# DESIGN7RA.net
KiCad netlist of a schematic drawn in EAGLE
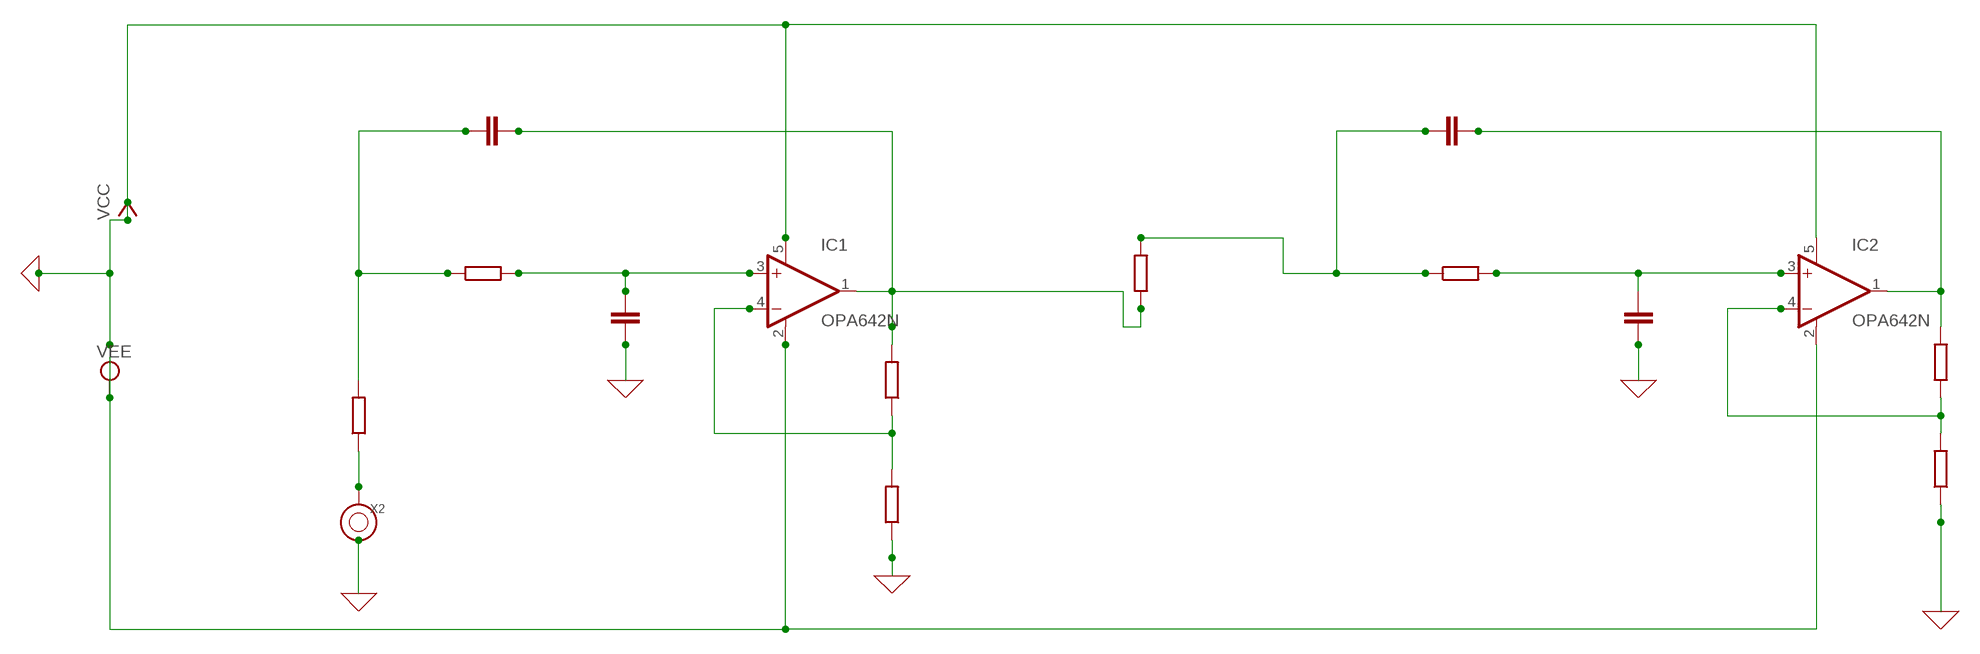
[diagram p0: schematic, sheet 1]

(export (version "E")
  (design (tool "Eeschema 10.0.6"))
  (components
    (comp (ref "IC1")
      (value "OPA642N")
      (footprint "eagle-import:SOT23-5")
      (libsource (lib "eagle-import") (part "OPA642N"))
    )
    (comp (ref "IC2")
      (value "OPA642N")
      (footprint "eagle-import:SOT23-5")
      (libsource (lib "eagle-import") (part "OPA642N"))
    )
    (comp (ref "X2")
      (value "BINDING-POST")
      (footprint "eagle-import:BINDING-POST")
      (libsource (lib "eagle-import") (part "BINDING-POST"))
    )
  )
  (nets
    (net (code "1") (name "GND") (class "Default")
      (node (ref "IC1") (pin "2") (pinfunction "V-_2") (pintype "power_in"))
      (node (ref "IC1") (pin "5") (pinfunction "V+_5") (pintype "power_in"))
      (node (ref "IC2") (pin "2") (pinfunction "V-_2") (pintype "power_in"))
      (node (ref "IC2") (pin "5") (pinfunction "V+_5") (pintype "power_in"))
    )
    (net (code "2") (name "Net-(X2-1-Pad1_1)") (class "Default")
      (node (ref "X2") (pin "1") (pinfunction "1_1") (pintype "passive"))
      (node (ref "X2") (pin "1_1") (pinfunction "1_1_1") (pintype "passive"))
      (node (ref "X2") (pin "1_2") (pinfunction "1_1_2") (pintype "passive"))
      (node (ref "X2") (pin "1_3") (pinfunction "1_1_3") (pintype "passive"))
      (node (ref "X2") (pin "1_4") (pinfunction "1_1_4") (pintype "passive"))
      (node (ref "X2") (pin "1_5") (pinfunction "1_1_5") (pintype "passive"))
      (node (ref "X2") (pin "1_6") (pinfunction "1_1_6") (pintype "passive"))
      (node (ref "X2") (pin "1_7") (pinfunction "1_1_7") (pintype "passive"))
      (node (ref "X2") (pin "1_8") (pinfunction "1_1_8") (pintype "passive"))
    )
    (net (code "3") (name "unconnected-(IC1-+IN-Pad3)") (class "Default")
      (node (ref "IC1") (pin "3") (pinfunction "+IN_3") (pintype "input"))
    )
    (net (code "4") (name "unconnected-(IC1--IN-Pad4)") (class "Default")
      (node (ref "IC1") (pin "4") (pinfunction "-IN_4") (pintype "input"))
    )
    (net (code "5") (name "unconnected-(IC1-OUT-Pad1)") (class "Default")
      (node (ref "IC1") (pin "1") (pinfunction "OUT_1") (pintype "output"))
    )
    (net (code "6") (name "unconnected-(IC2-+IN-Pad3)") (class "Default")
      (node (ref "IC2") (pin "3") (pinfunction "+IN_3") (pintype "input"))
    )
    (net (code "7") (name "unconnected-(IC2--IN-Pad4)") (class "Default")
      (node (ref "IC2") (pin "4") (pinfunction "-IN_4") (pintype "input"))
    )
    (net (code "8") (name "unconnected-(IC2-OUT-Pad1)") (class "Default")
      (node (ref "IC2") (pin "1") (pinfunction "OUT_1") (pintype "output"))
    )
  )
)
